# 7_ADC_Chip.net
KiCad netlist of a schematic drawn in Altium Designer
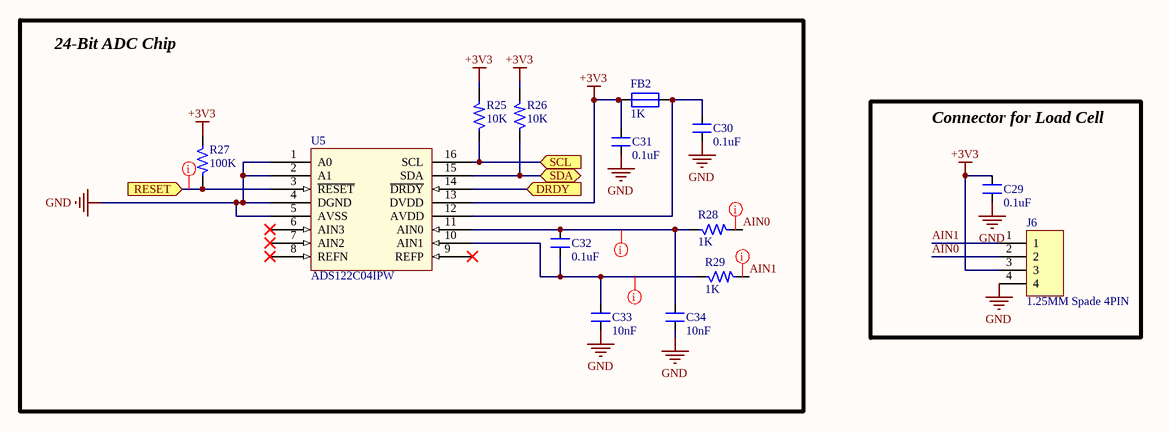
[diagram p0: [7] ADC Chip.SchDoc]

(export (version "E")
  (design (tool "Eeschema 10.0.6"))
  (components
    (comp (ref "C29")
      (value "0.1uF")
      (footprint "CAP_0805")
      (description "0.1µF ±10% 50V Ceramic Capacitor X7R 0805 (2012 Metric)")
      (fields
        (field (name "MANUFACTURER") "Samsung")
        (field (name "MANUFACTURER PART NUMBER") "CL21B104KBCNNNC")
      )
      (libsource (lib "ESTEEMPCBLIB") (part "CAP_0.1uF-50V-10%-0805"))
    )
    (comp (ref "C30")
      (value "0.1uF")
      (footprint "CAP_0805")
      (description "0.1µF ±10% 50V Ceramic Capacitor X7R 0805 (2012 Metric)")
      (fields
        (field (name "MANUFACTURER") "Samsung")
        (field (name "MANUFACTURER PART NUMBER") "CL21B104KBCNNNC")
      )
      (libsource (lib "ESTEEMPCBLIB") (part "CAP_0.1uF-50V-10%-0805"))
    )
    (comp (ref "C31")
      (value "0.1uF")
      (footprint "CAP_0805")
      (description "0.1µF ±10% 50V Ceramic Capacitor X7R 0805 (2012 Metric)")
      (fields
        (field (name "MANUFACTURER") "Samsung")
        (field (name "MANUFACTURER PART NUMBER") "CL21B104KBCNNNC")
      )
      (libsource (lib "ESTEEMPCBLIB") (part "CAP_0.1uF-50V-10%-0805"))
    )
    (comp (ref "C32")
      (value "0.1uF")
      (footprint "CAP_0805")
      (description "0.1µF ±10% 50V Ceramic Capacitor X7R 0805 (2012 Metric)")
      (fields
        (field (name "MANUFACTURER") "Samsung")
        (field (name "MANUFACTURER PART NUMBER") "CL21B104KBCNNNC")
      )
      (libsource (lib "ESTEEMPCBLIB") (part "CAP_0.1uF-50V-10%-0805"))
    )
    (comp (ref "C33")
      (value "10nF")
      (footprint "CAP_0805")
      (description "10000pF ±10% 50V Ceramic Capacitor X7R 0805 (2012 Metric)")
      (fields
        (field (name "MANUFACTURER") "Samsung")
        (field (name "MANUFACTURER PART NUMBER") "C0805C103K5RECAUTO")
      )
      (libsource (lib "ESTEEMPCBLIB") (part "CAP_10nF-50V-10%-0805"))
    )
    (comp (ref "C34")
      (value "10nF")
      (footprint "CAP_0805")
      (description "10000pF ±10% 50V Ceramic Capacitor X7R 0805 (2012 Metric)")
      (fields
        (field (name "MANUFACTURER") "Samsung")
        (field (name "MANUFACTURER PART NUMBER") "C0805C103K5RECAUTO")
      )
      (libsource (lib "ESTEEMPCBLIB") (part "CAP_10nF-50V-10%-0805"))
    )
    (comp (ref "FB2")
      (value "1K")
      (footprint "IND_0805")
      (description "1 kOhms @ 100MHz 1 Power Line Ferrite Bead 0805 (2012 Metric) 1.6A")
      (fields
        (field (name "MANUFACTURER") "Laird")
        (field (name "MANUFACTURER PART NUMBER") "BLM21SP102SH1D")
      )
      (libsource (lib "ESTEEMPCBLIB") (part "FB_1K-100MHZ-1.6A-0805"))
    )
    (comp (ref "J6")
      (value "1.25MM Spade 4PIN")
      (footprint "CON4_50_653004117322_TH_RA")
      (description "4 Pins, 1 Row 1.25mm Pitch, right angle Connector, male")
      (fields (field (name "MANUFACTURER PART NUMBER") "653004117322") (field (name "MANUFACTURER") "JST"))
      (libsource (lib "ESTEEMPCBLIB") (part "CON-PLG_4X1-50-RA-TH"))
    )
    (comp (ref "R25")
      (value "10K")
      (footprint "RES_0603")
      (description "10 kOhms ±1% 0.1W, 1/10W Chip Resistor 0603 (1608 Metric) Automotive AEC-Q200 Thick Film")
      (fields (field (name "MANUFACTURER") "Walsin") (field (name "MANUFACTURER PART NUMBER") "WR06X1002FTL"))
      (libsource (lib "ESTEEMPCBLIB") (part "RES_10K-0.1W-1%-0603"))
    )
    (comp (ref "R26")
      (value "10K")
      (footprint "RES_0603")
      (description "10 kOhms ±1% 0.1W, 1/10W Chip Resistor 0603 (1608 Metric) Automotive AEC-Q200 Thick Film")
      (fields (field (name "MANUFACTURER") "Walsin") (field (name "MANUFACTURER PART NUMBER") "WR06X1002FTL"))
      (libsource (lib "ESTEEMPCBLIB") (part "RES_10K-0.1W-1%-0603"))
    )
    (comp (ref "R27")
      (value "100K")
      (footprint "RES_0603")
      (description "100 kOhms ±1% 0.1W, 1/10W Chip Resistor 0603 (1608 Metric) Automotive AEC-Q200 Thick Film")
      (fields
        (field (name "MANUFACTURER") "Stackpole Electronics")
        (field (name "MANUFACTURER PART NUMBER") "RMCF0603FT100K")
      )
      (libsource (lib "ESTEEMPCBLIB") (part "RES_100K-0.1W-1%-0603"))
    )
    (comp (ref "R28")
      (value "1K")
      (footprint "RES_0603")
      (description "1 kOhms ±1% 0.1W, 1/10W Chip Resistor 0603 (1608 Metric) Automotive AEC-Q200 Thick Film")
      (fields (field (name "MANUFACTURER") "Walsin") (field (name "MANUFACTURER PART NUMBER") "WR06X1001FTL"))
      (libsource (lib "ESTEEMPCBLIB") (part "RES_1K-0.1W-1%-0603"))
    )
    (comp (ref "R29")
      (value "1K")
      (footprint "RES_0603")
      (description "1 kOhms ±1% 0.1W, 1/10W Chip Resistor 0603 (1608 Metric) Automotive AEC-Q200 Thick Film")
      (fields (field (name "MANUFACTURER") "Walsin") (field (name "MANUFACTURER PART NUMBER") "WR06X1001FTL"))
      (libsource (lib "ESTEEMPCBLIB") (part "RES_1K-0.1W-1%-0603"))
    )
    (comp (ref "U5")
      (value "ADS122C04IPW")
      (footprint "TSSOP16_25-59_294_54X14_SMT")
      (description "24 Bit Analog to Digital Converter 4 Input 1 Sigma-Delta 16-TSSOP")
      (fields (field (name "MANUFACTURER") "Texas Instruments"))
      (libsource (lib "ESTEEMPCBLIB") (part "IC_ADS122C04IPW"))
    )
  )
  (nets
    (net (code "1") (name "+3V3") (class "Default")
      (node (ref "C29") (pin "2") (pinfunction "2_2") (pintype "passive"))
      (node (ref "C31") (pin "2") (pinfunction "2_2") (pintype "passive"))
      (node (ref "FB2") (pin "1") (pinfunction "1_1") (pintype "passive"))
      (node (ref "J6") (pin "3") (pinfunction "3_3") (pintype "passive"))
      (node (ref "R25") (pin "2") (pinfunction "2_2") (pintype "passive"))
      (node (ref "R26") (pin "2") (pinfunction "2_2") (pintype "passive"))
      (node (ref "R27") (pin "1") (pinfunction "1_1") (pintype "passive"))
      (node (ref "U5") (pin "13") (pinfunction "DVDD_13") (pintype "power_in"))
    )
    (net (code "2") (name "/AIN0") (class "Default")
      (node (ref "J6") (pin "2") (pinfunction "2_2") (pintype "passive"))
      (node (ref "R28") (pin "2") (pinfunction "2_2") (pintype "passive"))
    )
    (net (code "3") (name "/AIN1") (class "Default")
      (node (ref "J6") (pin "1") (pinfunction "1_1") (pintype "passive"))
      (node (ref "R29") (pin "2") (pinfunction "2_2") (pintype "passive"))
    )
    (net (code "4") (name "/DRDY") (class "Default")
      (node (ref "U5") (pin "14") (pinfunction "DRDY_14") (pintype "input"))
    )
    (net (code "5") (name "/RESET") (class "Default")
      (node (ref "R27") (pin "2") (pinfunction "2_2") (pintype "passive"))
      (node (ref "U5") (pin "3") (pinfunction "RESET_3") (pintype "input"))
    )
    (net (code "6") (name "/SCL") (class "Default")
      (node (ref "R25") (pin "1") (pinfunction "1_1") (pintype "passive"))
      (node (ref "U5") (pin "16") (pinfunction "SCL_16") (pintype "open_collector"))
    )
    (net (code "7") (name "/SDA") (class "Default")
      (node (ref "R26") (pin "1") (pinfunction "1_1") (pintype "passive"))
      (node (ref "U5") (pin "15") (pinfunction "SDA_15") (pintype "open_collector"))
    )
    (net (code "8") (name "GND") (class "Default")
      (node (ref "C29") (pin "1") (pinfunction "1_1") (pintype "passive"))
      (node (ref "C30") (pin "1") (pinfunction "1_1") (pintype "passive"))
      (node (ref "C31") (pin "1") (pinfunction "1_1") (pintype "passive"))
      (node (ref "C33") (pin "2") (pinfunction "2_2") (pintype "passive"))
      (node (ref "C34") (pin "2") (pinfunction "2_2") (pintype "passive"))
      (node (ref "J6") (pin "4") (pinfunction "4_4") (pintype "passive"))
      (node (ref "U5") (pin "1") (pinfunction "A0_1") (pintype "passive"))
      (node (ref "U5") (pin "2") (pinfunction "A1_2") (pintype "passive"))
      (node (ref "U5") (pin "4") (pinfunction "DGND_4") (pintype "power_in"))
      (node (ref "U5") (pin "5") (pinfunction "AVSS_5") (pintype "power_in"))
    )
    (net (code "9") (name "Net-(U5-AIN0)") (class "Default")
      (node (ref "C32") (pin "2") (pinfunction "2_2") (pintype "passive"))
      (node (ref "C34") (pin "1") (pinfunction "1_1") (pintype "passive"))
      (node (ref "R28") (pin "1") (pinfunction "1_1") (pintype "passive"))
      (node (ref "U5") (pin "11") (pinfunction "AIN0_11") (pintype "input"))
    )
    (net (code "10") (name "Net-(U5-AIN1)") (class "Default")
      (node (ref "C32") (pin "1") (pinfunction "1_1") (pintype "passive"))
      (node (ref "C33") (pin "1") (pinfunction "1_1") (pintype "passive"))
      (node (ref "R29") (pin "1") (pinfunction "1_1") (pintype "passive"))
      (node (ref "U5") (pin "10") (pinfunction "AIN1_10") (pintype "input"))
    )
    (net (code "11") (name "Net-(U5-AVDD)") (class "Default")
      (node (ref "C30") (pin "2") (pinfunction "2_2") (pintype "passive"))
      (node (ref "FB2") (pin "2") (pinfunction "2_2") (pintype "passive"))
      (node (ref "U5") (pin "12") (pinfunction "AVDD_12") (pintype "power_in"))
    )
    (net (code "12") (name "unconnected-(U5-AIN2-Pad7)") (class "Default")
      (node (ref "U5") (pin "7") (pinfunction "AIN2_7") (pintype "input+no_connect"))
    )
    (net (code "13") (name "unconnected-(U5-AIN3-Pad6)") (class "Default")
      (node (ref "U5") (pin "6") (pinfunction "AIN3_6") (pintype "input+no_connect"))
    )
    (net (code "14") (name "unconnected-(U5-REFN-Pad8)") (class "Default")
      (node (ref "U5") (pin "8") (pinfunction "REFN_8") (pintype "input+no_connect"))
    )
    (net (code "15") (name "unconnected-(U5-REFP-Pad9)") (class "Default")
      (node (ref "U5") (pin "9") (pinfunction "REFP_9") (pintype "input+no_connect"))
    )
  )
)
